# SCH_nfc-card_2024-10-29.net
KiCad netlist of a schematic drawn in EasyEDA
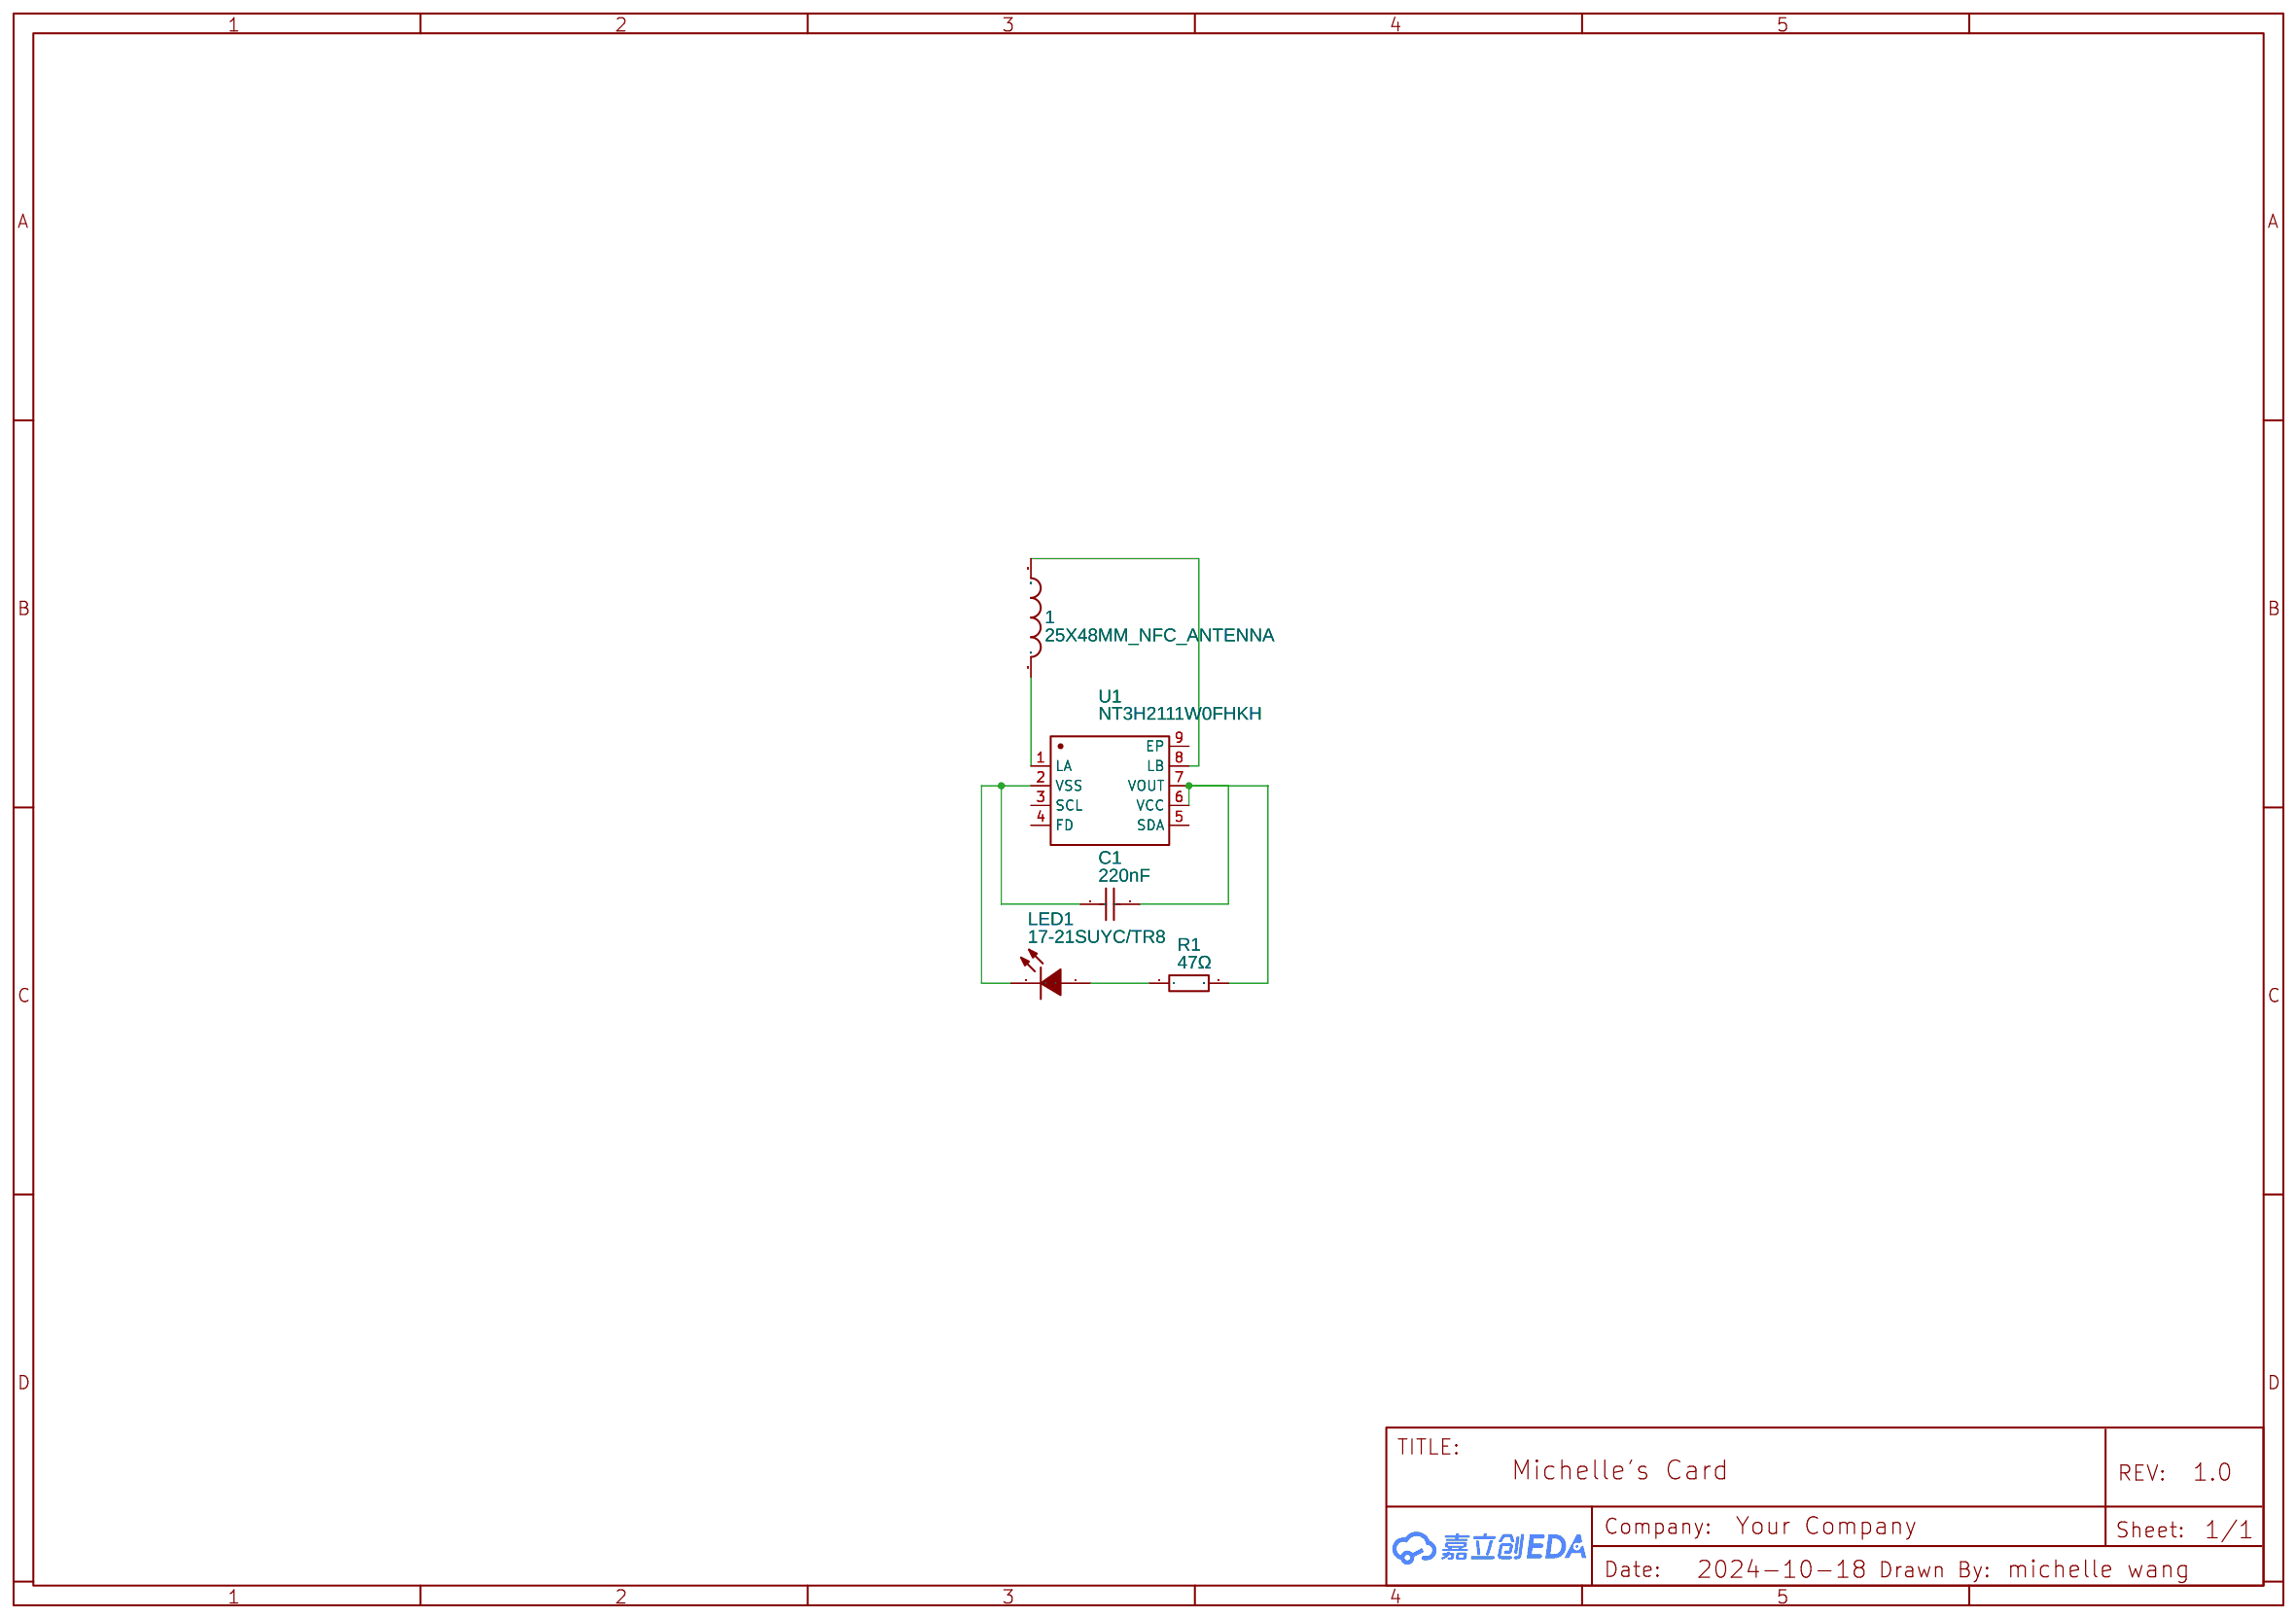
[diagram p0: schematic sheet]

(export (version "E")
  (design (tool "Eeschema 10.0.6"))
  (components
    (comp (ref "1") (value "25X48MM_NFC_ANTENNA") (libsource (lib "") (part "25X48MM_NFC_ANTENNA")))
    (comp (ref "C1")
      (value "220nF")
      (fields
        (field (name "Manufacturer Part") "CL10B224KA8NNNC")
        (field (name "Manufacturer") "SAMSUNG(三星)")
      )
      (libsource (lib "") (part "CL10B224KA8NNNC"))
    )
    (comp (ref "LED1")
      (value "17-21SUYC/TR8")
      (fields (field (name "Manufacturer Part") "KT-0805黄灯") (field (name "Manufacturer") "KENTO"))
      (libsource (lib "") (part "17-21SUYC/TR8"))
    )
    (comp (ref "R1")
      (value "47Ω")
      (fields
        (field (name "Manufacturer Part") "0603WAF470JT5E")
        (field (name "Manufacturer") "UNI-ROYAL(厚声)")
      )
      (libsource (lib "") (part "0603WAF470JT5E"))
    )
    (comp (ref "U1")
      (value "NT3H2111W0FHKH")
      (fields (field (name "Manufacturer") "NXP(恩智浦)"))
      (libsource (lib "") (part "NT3H2111W0FHKH"))
    )
  )
  (nets
    (net (code "1") (name "Net-(LED1-+)") (class "Default")
      (node (ref "LED1") (pin "1") (pinfunction "+_1") (pintype "unspecified"))
      (node (ref "R1") (pin "1") (pinfunction "1_1") (pintype "input"))
    )
    (net (code "2") (name "Net-(LED1--)") (class "Default")
      (node (ref "C1") (pin "1") (pinfunction "1_1") (pintype "input"))
      (node (ref "LED1") (pin "2") (pinfunction "-_2") (pintype "unspecified"))
      (node (ref "U1") (pin "2") (pinfunction "VSS_2") (pintype "unspecified"))
    )
    (net (code "3") (name "Net-(U1-LA)") (class "Default")
      (node (ref "1") (pin "P$2") (pinfunction "P$2_P$2") (pintype "bidirectional"))
      (node (ref "U1") (pin "1") (pinfunction "LA_1") (pintype "unspecified"))
    )
    (net (code "4") (name "Net-(U1-LB)") (class "Default")
      (node (ref "1") (pin "P$1") (pinfunction "P$1_P$1") (pintype "bidirectional"))
      (node (ref "U1") (pin "8") (pinfunction "LB_8") (pintype "unspecified"))
    )
    (net (code "5") (name "Net-(U1-VCC)") (class "Default")
      (node (ref "C1") (pin "2") (pinfunction "2_2") (pintype "input"))
      (node (ref "R1") (pin "2") (pinfunction "2_2") (pintype "input"))
      (node (ref "U1") (pin "6") (pinfunction "VCC_6") (pintype "unspecified"))
      (node (ref "U1") (pin "7") (pinfunction "VOUT_7") (pintype "unspecified"))
    )
    (net (code "6") (name "unconnected-(U1-EP-Pad9)") (class "Default")
      (node (ref "U1") (pin "9") (pinfunction "EP_9") (pintype "unspecified"))
    )
    (net (code "7") (name "unconnected-(U1-FD-Pad4)") (class "Default")
      (node (ref "U1") (pin "4") (pinfunction "FD_4") (pintype "unspecified"))
    )
    (net (code "8") (name "unconnected-(U1-SCL-Pad3)") (class "Default")
      (node (ref "U1") (pin "3") (pinfunction "SCL_3") (pintype "unspecified"))
    )
    (net (code "9") (name "unconnected-(U1-SDA-Pad5)") (class "Default")
      (node (ref "U1") (pin "5") (pinfunction "SDA_5") (pintype "unspecified"))
    )
  )
)
